# mini_project.net
KiCad netlist of a schematic drawn in Altium Designer
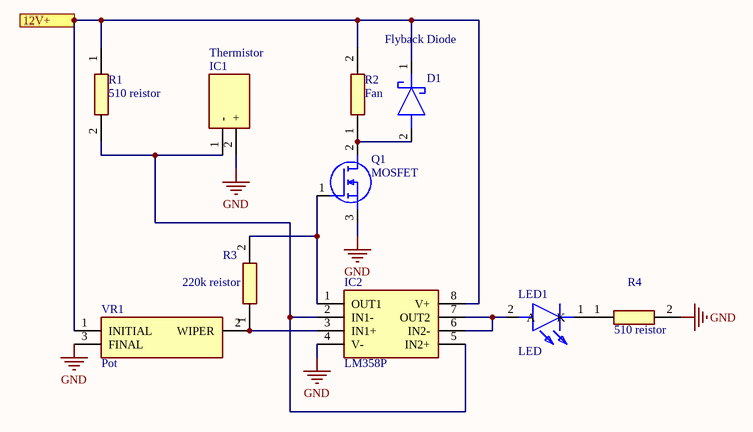
[diagram p0: mini_project.SchDoc]

(export (version "E")
  (design (tool "Eeschema 10.0.6"))
  (components
    (comp (ref "D1")
      (value "Flyback Diode")
      (footprint "SamacSys:DIOAD950W60L350D150")
      (description "SD101A-TR")
      (libsource (lib "*") (part "SD101A-TR"))
    )
    (comp (ref "IC1")
      (value "Thermistor")
      (footprint "SamacSys:LMT01QLPGQ1")
      (description "TMP6131LPGM")
      (libsource (lib "*") (part "TMP6131LPGM"))
    )
    (comp (ref "IC2")
      (value "LM358P")
      (footprint "SamacSys:DIP794W53P254L959H508Q8N")
      (description "Integrated Circuit")
      (fields (field (name "MOUSER2 PART NUMBER") "595-LM358P"))
      (libsource (lib "*") (part "LM358P"))
    )
    (comp (ref "LED1")
      (value "LED")
      (footprint "SamacSys:C543AWMNCCCKK141")
      (description "C543A-WMN-CCCKK141")
      (fields (field (name "MOUSER2 PART NUMBER") "941-C543AWMNCCCKK141"))
      (libsource (lib "*") (part "C543A-WMN-CCCKK141"))
    )
    (comp (ref "Q1")
      (value "MOSFET")
      (footprint "SamacSys:TO254P470X1016X2019-3P")
      (description "NTP095N65S3HF")
      (fields (field (name "MOUSER2 PART NUMBER") "863-NTP095N65S3HF"))
      (libsource (lib "*") (part "NTP095N65S3HF"))
    )
    (comp (ref "R1")
      (value "510 reistor")
      (footprint "SamacSys:RESAD3750W83L1670D520")
      (description "PR03000205100JAC00")
      (libsource (lib "") (part "PR03000205100JAC00_2"))
    )
    (comp (ref "R2")
      (value "Fan")
      (footprint "SamacSys:RESAD3750W83L1670D520")
      (description "PR03000205100JAC00")
      (libsource (lib "") (part "PR03000205100JAC00_1"))
    )
    (comp (ref "R3")
      (value "220k reistor")
      (footprint "SamacSys:RESAD3750W83L1670D520")
      (description "PR03000205100JAC00")
      (libsource (lib "") (part "PR03000205100JAC00_1"))
    )
    (comp (ref "R4")
      (value "510 reistor")
      (footprint "SamacSys:RESAD3750W83L1670D520")
      (description "PR03000205100JAC00")
      (libsource (lib "*") (part "PR03000205100JAC00"))
    )
    (comp (ref "VR1")
      (value "Pot")
      (footprint "SamacSys:PT10LV10224A2020PMS")
      (description "PT10LV10-224A2020-PM-S")
      (fields (field (name "MOUSER2 PART NUMBER") "531-PT1LV1224A22PMS"))
      (libsource (lib "*") (part "PT10LV10-224A2020-PM-S"))
    )
  )
  (nets
    (net (code "1") (name "/12V+") (class "Default")
      (node (ref "D1") (pin "1") (pinfunction "K_1") (pintype "passive"))
      (node (ref "IC2") (pin "8") (pinfunction "V+_8") (pintype "passive"))
      (node (ref "R1") (pin "1") (pinfunction "1_1") (pintype "passive"))
      (node (ref "R2") (pin "2") (pinfunction "2_2") (pintype "passive"))
      (node (ref "VR1") (pin "1") (pinfunction "INITIAL_1") (pintype "passive"))
    )
    (net (code "2") (name "GND") (class "Default")
      (node (ref "IC1") (pin "2") (pinfunction "+_2") (pintype "passive"))
      (node (ref "IC2") (pin "4") (pinfunction "V-_4") (pintype "passive"))
      (node (ref "Q1") (pin "3") (pinfunction "S_3") (pintype "passive"))
      (node (ref "R4") (pin "2") (pinfunction "2_2") (pintype "passive"))
      (node (ref "VR1") (pin "3") (pinfunction "FINAL_3") (pintype "passive"))
    )
    (net (code "3") (name "Net-(D1-A)") (class "Default")
      (node (ref "D1") (pin "2") (pinfunction "A_2") (pintype "passive"))
      (node (ref "Q1") (pin "2") (pinfunction "D_2") (pintype "passive"))
      (node (ref "R2") (pin "1") (pinfunction "1_1") (pintype "passive"))
    )
    (net (code "4") (name "Net-(IC1--)") (class "Default")
      (node (ref "IC1") (pin "1") (pinfunction "-_1") (pintype "passive"))
      (node (ref "IC2") (pin "2") (pinfunction "IN1-_2") (pintype "passive"))
      (node (ref "IC2") (pin "5") (pinfunction "IN2+_5") (pintype "passive"))
      (node (ref "R1") (pin "2") (pinfunction "2_2") (pintype "passive"))
    )
    (net (code "5") (name "Net-(IC2-IN1+)") (class "Default")
      (node (ref "IC2") (pin "3") (pinfunction "IN1+_3") (pintype "passive"))
      (node (ref "R3") (pin "1") (pinfunction "1_1") (pintype "passive"))
      (node (ref "VR1") (pin "2") (pinfunction "WIPER_2") (pintype "passive"))
    )
    (net (code "6") (name "Net-(IC2-IN2-)") (class "Default")
      (node (ref "IC2") (pin "6") (pinfunction "IN2-_6") (pintype "passive"))
      (node (ref "IC2") (pin "7") (pinfunction "OUT2_7") (pintype "passive"))
      (node (ref "LED1") (pin "2") (pinfunction "A_2") (pintype "passive"))
    )
    (net (code "7") (name "Net-(IC2-OUT1)") (class "Default")
      (node (ref "IC2") (pin "1") (pinfunction "OUT1_1") (pintype "passive"))
      (node (ref "Q1") (pin "1") (pinfunction "G_1") (pintype "passive"))
      (node (ref "R3") (pin "2") (pinfunction "2_2") (pintype "passive"))
    )
    (net (code "8") (name "Net-(LED1-K)") (class "Default")
      (node (ref "LED1") (pin "1") (pinfunction "K_1") (pintype "passive"))
      (node (ref "R4") (pin "1") (pinfunction "1_1") (pintype "passive"))
    )
  )
)
